# Peripheral.net
KiCad netlist of a schematic drawn in Altium Designer
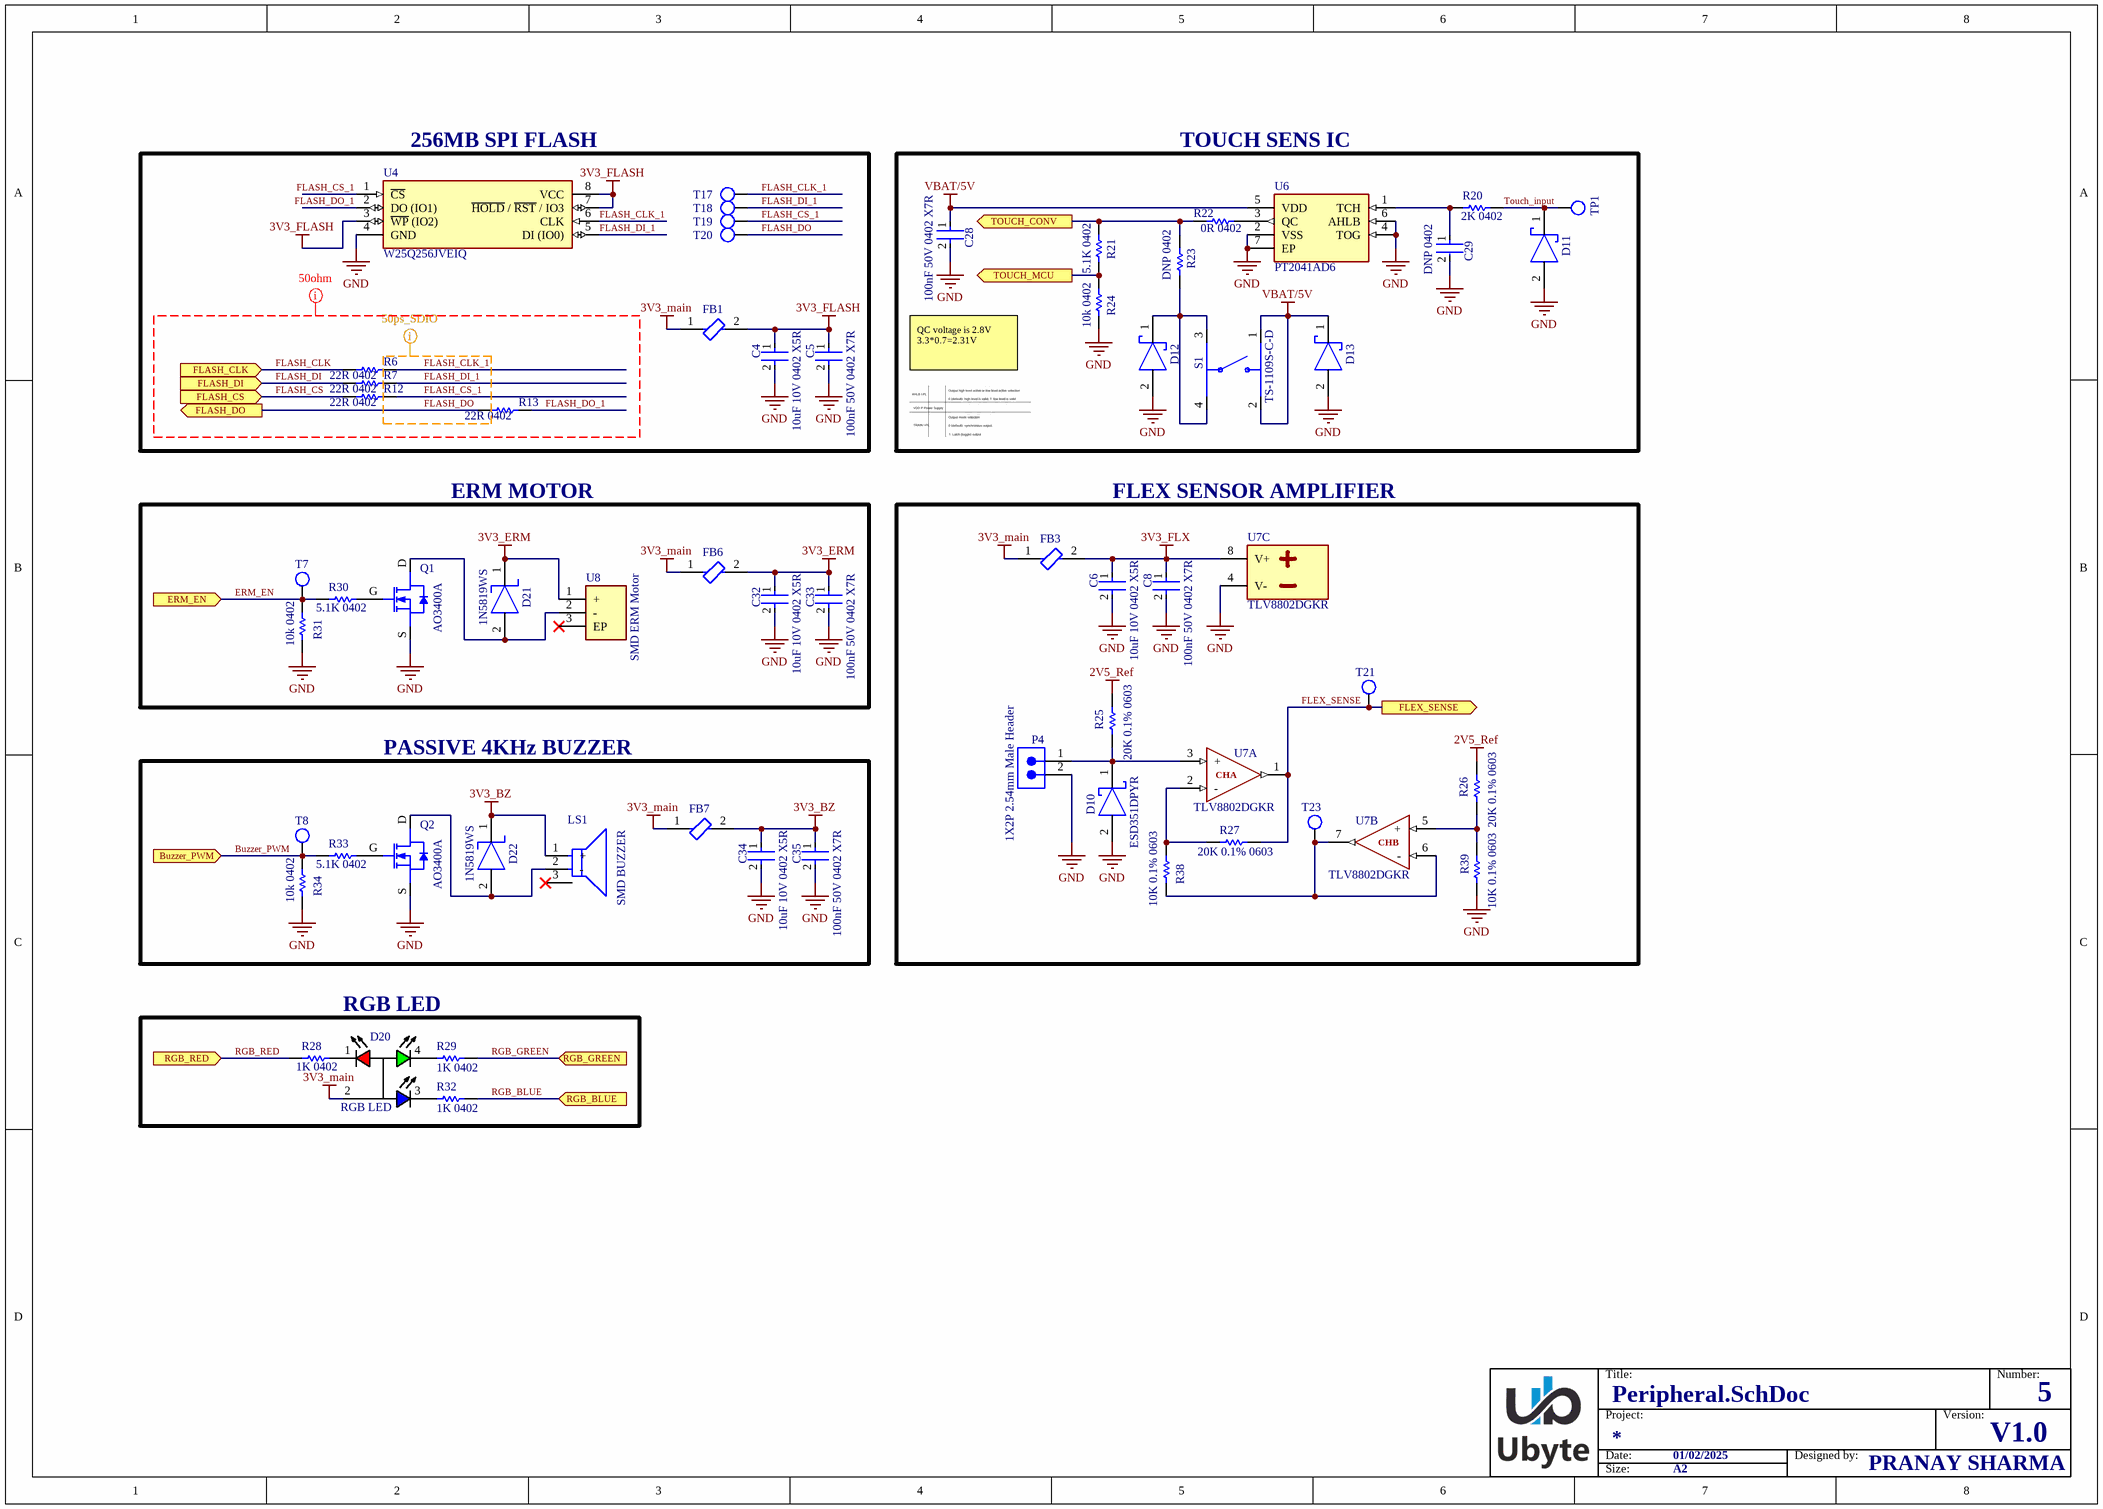
[diagram p0: Peripheral.SchDoc]

(export (version "E")
  (design (tool "Eeschema 10.0.6"))
  (components
    (comp (ref "C4")
      (value "10uF 10V 0402 X5R")
      (footprint "Res, Cap, Ind, LED, FB_Lib:0402 IPC CLASS C CAPACITOR")
      (libsource (lib "Capacitor_Lib") (part "10uF 10V 0402 X5R"))
    )
    (comp (ref "C5")
      (value "100nF 50V 0402 X7R")
      (footprint "Res, Cap, Ind, LED, FB_Lib:0402 IPC CLASS C CAPACITOR")
      (libsource (lib "Capacitor_Lib") (part "100nF 50V 0402 X7R"))
    )
    (comp (ref "C6")
      (value "10uF 10V 0402 X5R")
      (footprint "Res, Cap, Ind, LED, FB_Lib:0402 IPC CLASS C CAPACITOR")
      (libsource (lib "Capacitor_Lib") (part "10uF 10V 0402 X5R"))
    )
    (comp (ref "C8")
      (value "100nF 50V 0402 X7R")
      (footprint "Res, Cap, Ind, LED, FB_Lib:0402 IPC CLASS C CAPACITOR")
      (libsource (lib "Capacitor_Lib") (part "100nF 50V 0402 X7R"))
    )
    (comp (ref "C28")
      (value "100nF 50V 0402 X7R")
      (footprint "Res, Cap, Ind, LED, FB_Lib:0402 IPC CLASS C CAPACITOR")
      (libsource (lib "Capacitor_Lib") (part "100nF 50V 0402 X7R"))
    )
    (comp (ref "C29")
      (value "DNP 0402")
      (footprint "0402 IPC Class C Capacitor")
      (libsource (lib "Integrated Library V1.0") (part "Capacitor 0402"))
    )
    (comp (ref "C32")
      (value "10uF 10V 0402 X5R")
      (footprint "Res, Cap, Ind, LED, FB_Lib:0402 IPC CLASS C CAPACITOR")
      (libsource (lib "Capacitor_Lib") (part "10uF 10V 0402 X5R"))
    )
    (comp (ref "C33")
      (value "100nF 50V 0402 X7R")
      (footprint "Res, Cap, Ind, LED, FB_Lib:0402 IPC CLASS C CAPACITOR")
      (libsource (lib "Capacitor_Lib") (part "100nF 50V 0402 X7R"))
    )
    (comp (ref "C34")
      (value "10uF 10V 0402 X5R")
      (footprint "Res, Cap, Ind, LED, FB_Lib:0402 IPC CLASS C CAPACITOR")
      (libsource (lib "Capacitor_Lib") (part "10uF 10V 0402 X5R"))
    )
    (comp (ref "C35")
      (value "100nF 50V 0402 X7R")
      (footprint "Res, Cap, Ind, LED, FB_Lib:0402 IPC CLASS C CAPACITOR")
      (libsource (lib "Capacitor_Lib") (part "100nF 50V 0402 X7R"))
    )
    (comp (ref "D10")
      (value "ESD351DPYR")
      (footprint "Res, Cap, Ind, LED, FB_Lib:DPY0002A IPC-C")
      (libsource (lib "Diodes_Lib") (part "ESD351DPYR"))
    )
    (comp (ref "D11")
      (value "SP3031-01ETG")
      (footprint "Res, Cap, Ind, LED, FB_Lib:SOD882 IPC-C")
      (libsource (lib "Diodes_Lib") (part "SP3031-01ETG"))
    )
    (comp (ref "D12")
      (value "SP3031-01ETG")
      (footprint "Res, Cap, Ind, LED, FB_Lib:SOD882 IPC-C")
      (libsource (lib "Diodes_Lib") (part "SP3031-01ETG"))
    )
    (comp (ref "D13")
      (value "SP3031-01ETG")
      (footprint "Res, Cap, Ind, LED, FB_Lib:SOD882 IPC-C")
      (libsource (lib "Diodes_Lib") (part "SP3031-01ETG"))
    )
    (comp (ref "D20")
      (value "RGB LED")
      (footprint "Res, Cap, Ind, LED, FB_Lib:NH-B1515RGBA-HF IPC-C")
      (libsource (lib "Diodes_Lib") (part "NH-B1515RGBA-HF"))
    )
    (comp (ref "D21")
      (value "1N5819WS")
      (footprint "Res, Cap, Ind, LED, FB_Lib:SOD-323 IPC-C")
      (libsource (lib "Diodes_Lib") (part "1N5819WS"))
    )
    (comp (ref "D22")
      (value "1N5819WS")
      (footprint "Res, Cap, Ind, LED, FB_Lib:SOD-323 IPC-C")
      (libsource (lib "Diodes_Lib") (part "1N5819WS"))
    )
    (comp (ref "FB1")
      (value "BLM15AX102SN1D")
      (footprint "Res, Cap, Ind, LED, FB_Lib:0402 IPC CLASS C FERRITE BEAD")
      (libsource (lib "Ferrite_Bead_Lib") (part "BLM15AX102SN1D"))
    )
    (comp (ref "FB3")
      (value "BLM15AX102SN1D")
      (footprint "Res, Cap, Ind, LED, FB_Lib:0402 IPC CLASS C FERRITE BEAD")
      (libsource (lib "Ferrite_Bead_Lib") (part "BLM15AX102SN1D"))
    )
    (comp (ref "FB6")
      (value "BLM15AX102SN1D")
      (footprint "Res, Cap, Ind, LED, FB_Lib:0402 IPC CLASS C FERRITE BEAD")
      (libsource (lib "Ferrite_Bead_Lib") (part "BLM15AX102SN1D"))
    )
    (comp (ref "FB7")
      (value "BLM15AX102SN1D")
      (footprint "Res, Cap, Ind, LED, FB_Lib:0402 IPC CLASS C FERRITE BEAD")
      (libsource (lib "Ferrite_Bead_Lib") (part "BLM15AX102SN1D"))
    )
    (comp (ref "LS1")
      (value "SMD BUZZER")
      (footprint "Miscellaneous_Lib:MLT-5020")
      (libsource (lib "Miscellaneous_Lib") (part "MLT-5020"))
    )
    (comp (ref "P4")
      (value "1X2P 2.54mm Male Header")
      (footprint "Connectors_Lib:2P 2.54mm Open Header")
      (libsource (lib "Connectors_Lib") (part "1X2P 2.54mm Male Header"))
    )
    (comp (ref "Q1")
      (value "AO3400A")
      (footprint "Transistors_Lib:SOT-23 IPC-C")
      (libsource (lib "Transistors_Lib") (part "AO3400A"))
    )
    (comp (ref "Q2")
      (value "AO3400A")
      (footprint "Transistors_Lib:SOT-23 IPC-C")
      (libsource (lib "Transistors_Lib") (part "AO3400A"))
    )
    (comp (ref "R6")
      (value "22R 0402")
      (footprint "Res, Cap, Ind, LED, FB_Lib:0402 IPC CLASS C RESISTOR")
      (libsource (lib "Resistor_Lib") (part "22R 1% 0402"))
    )
    (comp (ref "R7")
      (value "22R 0402")
      (footprint "Res, Cap, Ind, LED, FB_Lib:0402 IPC CLASS C RESISTOR")
      (libsource (lib "Resistor_Lib") (part "22R 1% 0402"))
    )
    (comp (ref "R12")
      (value "22R 0402")
      (footprint "Res, Cap, Ind, LED, FB_Lib:0402 IPC CLASS C RESISTOR")
      (libsource (lib "Resistor_Lib") (part "22R 1% 0402"))
    )
    (comp (ref "R13")
      (value "22R 0402")
      (footprint "Res, Cap, Ind, LED, FB_Lib:0402 IPC CLASS C RESISTOR")
      (libsource (lib "Resistor_Lib") (part "22R 1% 0402"))
    )
    (comp (ref "R20")
      (value "2K 0402")
      (footprint "Res, Cap, Ind, LED, FB_Lib:0402 IPC CLASS C RESISTOR")
      (libsource (lib "Resistor_Lib") (part "2K 1% 0402"))
    )
    (comp (ref "R21")
      (value "5.1K 0402")
      (footprint "Res, Cap, Ind, LED, FB_Lib:0402 IPC CLASS C RESISTOR")
      (libsource (lib "Resistor_Lib") (part "5.1K 1% 0402"))
    )
    (comp (ref "R22")
      (value "0R 0402")
      (footprint "Res, Cap, Ind, LED, FB_Lib:0402 IPC CLASS B RESISTOR")
      (libsource (lib "Resistor_Lib") (part "0R 1% 0402"))
    )
    (comp (ref "R23")
      (value "DNP 0402")
      (footprint "Res, Cap, Ind, LED, FB_Lib:0402 IPC CLASS B RESISTOR")
      (libsource (lib "Resistor_Lib") (part "0R 1% 0402"))
    )
    (comp (ref "R24")
      (value "10k 0402")
      (footprint "Res, Cap, Ind, LED, FB_Lib:0402 IPC CLASS C RESISTOR")
      (libsource (lib "Resistor_Lib") (part "10k 1% 0402"))
    )
    (comp (ref "R25")
      (value "20K 0.1% 0603")
      (footprint "Res, Cap, Ind, LED, FB_Lib:0603 IPC CLASS C RESISTOR")
      (libsource (lib "Resistor_Lib") (part "20K 0.1% 0603"))
    )
    (comp (ref "R26")
      (value "20K 0.1% 0603")
      (footprint "Res, Cap, Ind, LED, FB_Lib:0603 IPC CLASS C RESISTOR")
      (libsource (lib "Resistor_Lib") (part "20K 0.1% 0603"))
    )
    (comp (ref "R27")
      (value "20K 0.1% 0603")
      (footprint "Res, Cap, Ind, LED, FB_Lib:0603 IPC CLASS C RESISTOR")
      (libsource (lib "Resistor_Lib") (part "20K 0.1% 0603"))
    )
    (comp (ref "R28")
      (value "1K 0402")
      (footprint "Res, Cap, Ind, LED, FB_Lib:0402 IPC CLASS C RESISTOR")
      (libsource (lib "Resistor_Lib") (part "1K 1% 0402"))
    )
    (comp (ref "R29")
      (value "1K 0402")
      (footprint "Res, Cap, Ind, LED, FB_Lib:0402 IPC CLASS C RESISTOR")
      (libsource (lib "Resistor_Lib") (part "1K 1% 0402"))
    )
    (comp (ref "R30")
      (value "5.1K 0402")
      (footprint "Res, Cap, Ind, LED, FB_Lib:0402 IPC CLASS C RESISTOR")
      (libsource (lib "Resistor_Lib") (part "5.1K 1% 0402"))
    )
    (comp (ref "R31")
      (value "10k 0402")
      (footprint "Res, Cap, Ind, LED, FB_Lib:0402 IPC CLASS C RESISTOR")
      (libsource (lib "Resistor_Lib") (part "10k 1% 0402"))
    )
    (comp (ref "R32")
      (value "1K 0402")
      (footprint "Res, Cap, Ind, LED, FB_Lib:0402 IPC CLASS C RESISTOR")
      (libsource (lib "Resistor_Lib") (part "1K 1% 0402"))
    )
    (comp (ref "R33")
      (value "5.1K 0402")
      (footprint "Res, Cap, Ind, LED, FB_Lib:0402 IPC CLASS C RESISTOR")
      (libsource (lib "Resistor_Lib") (part "5.1K 1% 0402"))
    )
    (comp (ref "R34")
      (value "10k 0402")
      (footprint "Res, Cap, Ind, LED, FB_Lib:0402 IPC CLASS C RESISTOR")
      (libsource (lib "Resistor_Lib") (part "10k 1% 0402"))
    )
    (comp (ref "R38")
      (value "10K 0.1% 0603")
      (footprint "Res, Cap, Ind, LED, FB_Lib:0603 IPC CLASS C RESISTOR")
      (libsource (lib "Resistor_Lib") (part "10K 0.1% 0603"))
    )
    (comp (ref "R39")
      (value "10K 0.1% 0603")
      (footprint "Res, Cap, Ind, LED, FB_Lib:0603 IPC CLASS C RESISTOR")
      (libsource (lib "Resistor_Lib") (part "10K 0.1% 0603"))
    )
    (comp (ref "S1")
      (value "TS-1109S-C-D")
      (footprint "TS-1127-C")
      (libsource (lib "Integrated Library V1.0") (part "TS-1127-C"))
    )
    (comp (ref "T7")
      (value "~")
      (footprint "Test Point TH")
      (libsource (lib "Miscellaneous_Lib") (part "Test Point TH"))
    )
    (comp (ref "T8")
      (value "~")
      (footprint "Test Point TH")
      (libsource (lib "Miscellaneous_Lib") (part "Test Point TH"))
    )
    (comp (ref "T17")
      (value "TP")
      (footprint "Miscellaneous_Lib:Testpoint1")
      (libsource (lib "Miscellaneous_Lib") (part "Testpoint1"))
    )
    (comp (ref "T18")
      (value "TP")
      (footprint "Miscellaneous_Lib:Testpoint1")
      (libsource (lib "Miscellaneous_Lib") (part "Testpoint1"))
    )
    (comp (ref "T19")
      (value "TP")
      (footprint "Miscellaneous_Lib:Testpoint1")
      (libsource (lib "Miscellaneous_Lib") (part "Testpoint1"))
    )
    (comp (ref "T20")
      (value "TP")
      (footprint "Miscellaneous_Lib:Testpoint1")
      (libsource (lib "Miscellaneous_Lib") (part "Testpoint1"))
    )
    (comp (ref "T21")
      (value "TP")
      (footprint "Miscellaneous_Lib:Testpoint1")
      (libsource (lib "Miscellaneous_Lib") (part "Testpoint1"))
    )
    (comp (ref "T23")
      (value "TP")
      (footprint "Miscellaneous_Lib:Testpoint1")
      (libsource (lib "Miscellaneous_Lib") (part "Testpoint1"))
    )
    (comp (ref "TP1")
      (value "Test Point TH")
      (footprint "Test Point TH")
      (libsource (lib "Integrated Library V1.0") (part "Test Point TH"))
    )
    (comp (ref "U4")
      (value "W25Q256JVEIQ")
      (footprint "Integrated_Circuits_Lib:8-Pad WSON 8x6-mm IPC-C")
      (libsource (lib "Integrated_Circuits_Lib") (part "W25Q256JVEIQ"))
    )
    (comp (ref "U6")
      (value "PT2041AD6")
      (footprint "Integrated_Circuits_Lib:DFN2X2-6L IPC-C")
      (libsource (lib "Integrated_Circuits_Lib") (part "PT2041AD6"))
    )
    (comp (ref "U7")
      (value "TLV8802DGKR")
      (footprint "Integrated_Circuits_Lib:DGK0008A IPC-C")
      (libsource (lib "Integrated_Circuits_Lib") (part "TLV8802DGKR"))
    )
    (comp (ref "U8")
      (value "SMD ERM Motor")
      (footprint "Miscellaneous_Lib:Z3OC1T8219731")
      (libsource (lib "Miscellaneous_Lib") (part "Z3OC1T8219731"))
    )
  )
  (nets
    (net (code "1") (name "/Buzzer_PWM") (class "Default")
      (node (ref "R33") (pin "1") (pinfunction "1_1") (pintype "passive"))
      (node (ref "R34") (pin "2") (pinfunction "2_2") (pintype "passive"))
      (node (ref "T8") (pin "0") (pinfunction "0_0") (pintype "passive"))
    )
    (net (code "2") (name "/ERM_EN") (class "Default")
      (node (ref "R30") (pin "1") (pinfunction "1_1") (pintype "passive"))
      (node (ref "R31") (pin "2") (pinfunction "2_2") (pintype "passive"))
      (node (ref "T7") (pin "0") (pinfunction "0_0") (pintype "passive"))
    )
    (net (code "3") (name "/FLASH_CLK") (class "Default")
      (node (ref "R6") (pin "1") (pinfunction "1_1") (pintype "passive"))
    )
    (net (code "4") (name "/FLASH_CLK_1") (class "Default")
      (node (ref "R6") (pin "2") (pinfunction "2_2") (pintype "passive"))
      (node (ref "T17") (pin "0") (pinfunction "0_0") (pintype "passive"))
      (node (ref "U4") (pin "6") (pinfunction "CLK_6") (pintype "input"))
    )
    (net (code "5") (name "/FLASH_CS") (class "Default")
      (node (ref "R12") (pin "1") (pinfunction "1_1") (pintype "passive"))
    )
    (net (code "6") (name "/FLASH_CS_1") (class "Default")
      (node (ref "R12") (pin "2") (pinfunction "2_2") (pintype "passive"))
      (node (ref "T19") (pin "0") (pinfunction "0_0") (pintype "passive"))
      (node (ref "U4") (pin "1") (pinfunction "~{CS}_1") (pintype "input"))
    )
    (net (code "7") (name "/FLASH_DI") (class "Default")
      (node (ref "R7") (pin "1") (pinfunction "1_1") (pintype "passive"))
    )
    (net (code "8") (name "/FLASH_DI_1") (class "Default")
      (node (ref "R7") (pin "2") (pinfunction "2_2") (pintype "passive"))
      (node (ref "T18") (pin "0") (pinfunction "0_0") (pintype "passive"))
      (node (ref "U4") (pin "5") (pinfunction "DI_(IO0)_5") (pintype "bidirectional"))
    )
    (net (code "9") (name "/FLASH_DO") (class "Default")
      (node (ref "R13") (pin "1") (pinfunction "1_1") (pintype "passive"))
      (node (ref "T20") (pin "0") (pinfunction "0_0") (pintype "passive"))
    )
    (net (code "10") (name "/FLASH_DO_1") (class "Default")
      (node (ref "R13") (pin "2") (pinfunction "2_2") (pintype "passive"))
      (node (ref "U4") (pin "2") (pinfunction "DO_(IO1)_2") (pintype "bidirectional"))
    )
    (net (code "11") (name "/FLEX_SENSE") (class "Default")
      (node (ref "R27") (pin "1") (pinfunction "1_1") (pintype "passive"))
      (node (ref "T21") (pin "0") (pinfunction "0_0") (pintype "passive"))
      (node (ref "U7") (pin "1") (pinfunction "OUT1_1") (pintype "output"))
    )
    (net (code "12") (name "/RGB_BLUE") (class "Default")
      (node (ref "R32") (pin "2") (pinfunction "2_2") (pintype "passive"))
    )
    (net (code "13") (name "/RGB_GREEN") (class "Default")
      (node (ref "R29") (pin "2") (pinfunction "2_2") (pintype "passive"))
    )
    (net (code "14") (name "/RGB_RED") (class "Default")
      (node (ref "R28") (pin "1") (pinfunction "1_1") (pintype "passive"))
    )
    (net (code "15") (name "/TOUCH_CONV") (class "Default")
      (node (ref "R21") (pin "2") (pinfunction "2_2") (pintype "passive"))
      (node (ref "R22") (pin "2") (pinfunction "2_2") (pintype "passive"))
      (node (ref "R23") (pin "1") (pinfunction "1_1") (pintype "passive"))
    )
    (net (code "16") (name "/TOUCH_MCU") (class "Default")
      (node (ref "R21") (pin "1") (pinfunction "1_1") (pintype "passive"))
      (node (ref "R24") (pin "1") (pinfunction "1_1") (pintype "passive"))
    )
    (net (code "17") (name "/Touch_input") (class "Default")
      (node (ref "D11") (pin "1") (pinfunction "C_1") (pintype "passive"))
      (node (ref "R20") (pin "2") (pinfunction "2_2") (pintype "passive"))
      (node (ref "TP1") (pin "0") (pinfunction "0_0") (pintype "passive"))
    )
    (net (code "18") (name "2V5_Ref") (class "Default")
      (node (ref "R25") (pin "2") (pinfunction "2_2") (pintype "passive"))
      (node (ref "R26") (pin "2") (pinfunction "2_2") (pintype "passive"))
    )
    (net (code "19") (name "3V3_BZ") (class "Default")
      (node (ref "C34") (pin "1") (pinfunction "1_1") (pintype "passive"))
      (node (ref "C35") (pin "1") (pinfunction "1_1") (pintype "passive"))
      (node (ref "D22") (pin "1") (pinfunction "C_1") (pintype "passive"))
      (node (ref "FB7") (pin "2") (pinfunction "2_2") (pintype "passive"))
      (node (ref "LS1") (pin "1") (pinfunction "+_1") (pintype "passive"))
    )
    (net (code "20") (name "3V3_ERM") (class "Default")
      (node (ref "C32") (pin "1") (pinfunction "1_1") (pintype "passive"))
      (node (ref "C33") (pin "1") (pinfunction "1_1") (pintype "passive"))
      (node (ref "D21") (pin "1") (pinfunction "C_1") (pintype "passive"))
      (node (ref "FB6") (pin "2") (pinfunction "2_2") (pintype "passive"))
      (node (ref "U8") (pin "1") (pinfunction "+_1") (pintype "power_in"))
    )
    (net (code "21") (name "3V3_FLASH") (class "Default")
      (node (ref "C4") (pin "1") (pinfunction "1_1") (pintype "passive"))
      (node (ref "C5") (pin "1") (pinfunction "1_1") (pintype "passive"))
      (node (ref "FB1") (pin "2") (pinfunction "2_2") (pintype "passive"))
      (node (ref "U4") (pin "3") (pinfunction "~{WP}_(IO2)_3") (pintype "bidirectional"))
      (node (ref "U4") (pin "7") (pinfunction "~{HOLD}_/_~{RST}_/_IO3_7") (pintype "bidirectional"))
      (node (ref "U4") (pin "8") (pinfunction "VCC_8") (pintype "power_in"))
    )
    (net (code "22") (name "3V3_FLX") (class "Default")
      (node (ref "C6") (pin "1") (pinfunction "1_1") (pintype "passive"))
      (node (ref "C8") (pin "1") (pinfunction "1_1") (pintype "passive"))
      (node (ref "FB3") (pin "2") (pinfunction "2_2") (pintype "passive"))
      (node (ref "U7") (pin "8") (pinfunction "V+_8") (pintype "power_in"))
    )
    (net (code "23") (name "3V3_main") (class "Default")
      (node (ref "D20") (pin "2") (pinfunction "COM+_2") (pintype "passive"))
      (node (ref "FB1") (pin "1") (pinfunction "1_1") (pintype "passive"))
      (node (ref "FB3") (pin "1") (pinfunction "1_1") (pintype "passive"))
      (node (ref "FB6") (pin "1") (pinfunction "1_1") (pintype "passive"))
      (node (ref "FB7") (pin "1") (pinfunction "1_1") (pintype "passive"))
    )
    (net (code "24") (name "GND") (class "Default")
      (node (ref "C28") (pin "2") (pinfunction "2_2") (pintype "passive"))
      (node (ref "C29") (pin "2") (pinfunction "2_2") (pintype "passive"))
      (node (ref "C32") (pin "2") (pinfunction "2_2") (pintype "passive"))
      (node (ref "C33") (pin "2") (pinfunction "2_2") (pintype "passive"))
      (node (ref "C34") (pin "2") (pinfunction "2_2") (pintype "passive"))
      (node (ref "C35") (pin "2") (pinfunction "2_2") (pintype "passive"))
      (node (ref "C4") (pin "2") (pinfunction "2_2") (pintype "passive"))
      (node (ref "C5") (pin "2") (pinfunction "2_2") (pintype "passive"))
      (node (ref "C6") (pin "2") (pinfunction "2_2") (pintype "passive"))
      (node (ref "C8") (pin "2") (pinfunction "2_2") (pintype "passive"))
      (node (ref "D10") (pin "2") (pinfunction "K2_2") (pintype "passive"))
      (node (ref "D11") (pin "2") (pinfunction "A_2") (pintype "passive"))
      (node (ref "D12") (pin "2") (pinfunction "A_2") (pintype "passive"))
      (node (ref "D13") (pin "2") (pinfunction "A_2") (pintype "passive"))
      (node (ref "P4") (pin "2") (pinfunction "2_2") (pintype "passive"))
      (node (ref "Q1") (pin "S") (pinfunction "SOURCE_S") (pintype "passive"))
      (node (ref "Q2") (pin "S") (pinfunction "SOURCE_S") (pintype "passive"))
      (node (ref "R24") (pin "2") (pinfunction "2_2") (pintype "passive"))
      (node (ref "R31") (pin "1") (pinfunction "1_1") (pintype "passive"))
      (node (ref "R34") (pin "1") (pinfunction "1_1") (pintype "passive"))
      (node (ref "R39") (pin "1") (pinfunction "1_1") (pintype "passive"))
      (node (ref "U4") (pin "4") (pinfunction "GND_4") (pintype "power_in"))
      (node (ref "U6") (pin "2") (pinfunction "VSS_2") (pintype "power_in"))
      (node (ref "U6") (pin "4") (pinfunction "TOG_4") (pintype "input"))
      (node (ref "U6") (pin "6") (pinfunction "AHLB_6") (pintype "input"))
      (node (ref "U6") (pin "7") (pinfunction "EP_7") (pintype "power_in"))
      (node (ref "U7") (pin "4") (pinfunction "V-_4") (pintype "power_in"))
    )
    (net (code "25") (name "Net-(D10-K1)") (class "Default")
      (node (ref "D10") (pin "1") (pinfunction "K1_1") (pintype "passive"))
      (node (ref "P4") (pin "1") (pinfunction "1_1") (pintype "passive"))
      (node (ref "R25") (pin "1") (pinfunction "1_1") (pintype "passive"))
      (node (ref "U7") (pin "3") (pinfunction "+_3") (pintype "input"))
    )
    (net (code "26") (name "Net-(D12-C)") (class "Default")
      (node (ref "D12") (pin "1") (pinfunction "C_1") (pintype "passive"))
      (node (ref "R23") (pin "2") (pinfunction "2_2") (pintype "passive"))
      (node (ref "S1") (pin "3") (pinfunction "3_3") (pintype "passive"))
      (node (ref "S1") (pin "4") (pinfunction "4_4") (pintype "passive"))
    )
    (net (code "27") (name "Net-(D20-B-)") (class "Default")
      (node (ref "D20") (pin "3") (pinfunction "B-_3") (pintype "passive"))
      (node (ref "R32") (pin "1") (pinfunction "1_1") (pintype "passive"))
    )
    (net (code "28") (name "Net-(D20-G-)") (class "Default")
      (node (ref "D20") (pin "4") (pinfunction "G-_4") (pintype "passive"))
      (node (ref "R29") (pin "1") (pinfunction "1_1") (pintype "passive"))
    )
    (net (code "29") (name "Net-(D20-R-)") (class "Default")
      (node (ref "D20") (pin "1") (pinfunction "R-_1") (pintype "passive"))
      (node (ref "R28") (pin "2") (pinfunction "2_2") (pintype "passive"))
    )
    (net (code "30") (name "Net-(D21-A)") (class "Default")
      (node (ref "D21") (pin "2") (pinfunction "A_2") (pintype "passive"))
      (node (ref "Q1") (pin "D") (pinfunction "DRAIN_D") (pintype "passive"))
      (node (ref "U8") (pin "2") (pinfunction "-_2") (pintype "power_in"))
    )
    (net (code "31") (name "Net-(D22-A)") (class "Default")
      (node (ref "D22") (pin "2") (pinfunction "A_2") (pintype "passive"))
      (node (ref "LS1") (pin "2") (pinfunction "-_2") (pintype "passive"))
      (node (ref "Q2") (pin "D") (pinfunction "DRAIN_D") (pintype "passive"))
    )
    (net (code "32") (name "Net-(Q1-GATE)") (class "Default")
      (node (ref "Q1") (pin "G") (pinfunction "GATE_G") (pintype "passive"))
      (node (ref "R30") (pin "2") (pinfunction "2_2") (pintype "passive"))
    )
    (net (code "33") (name "Net-(Q2-GATE)") (class "Default")
      (node (ref "Q2") (pin "G") (pinfunction "GATE_G") (pintype "passive"))
      (node (ref "R33") (pin "2") (pinfunction "2_2") (pintype "passive"))
    )
    (net (code "34") (name "Net-(U6-QC)") (class "Default")
      (node (ref "R22") (pin "1") (pinfunction "1_1") (pintype "passive"))
      (node (ref "U6") (pin "3") (pinfunction "QC_3") (pintype "output"))
    )
    (net (code "35") (name "Net-(U6-TCH)") (class "Default")
      (node (ref "C29") (pin "1") (pinfunction "1_1") (pintype "passive"))
      (node (ref "R20") (pin "1") (pinfunction "1_1") (pintype "passive"))
      (node (ref "U6") (pin "1") (pinfunction "TCH_1") (pintype "input"))
    )
    (net (code "36") (name "Net-(U7A--)") (class "Default")
      (node (ref "R27") (pin "2") (pinfunction "2_2") (pintype "passive"))
      (node (ref "R38") (pin "2") (pinfunction "2_2") (pintype "passive"))
      (node (ref "U7") (pin "2") (pinfunction "-_2") (pintype "input"))
    )
    (net (code "37") (name "Net-(U7B-+)") (class "Default")
      (node (ref "R26") (pin "1") (pinfunction "1_1") (pintype "passive"))
      (node (ref "R39") (pin "2") (pinfunction "2_2") (pintype "passive"))
      (node (ref "U7") (pin "5") (pinfunction "+_5") (pintype "input"))
    )
    (net (code "38") (name "Net-(U7B--)") (class "Default")
      (node (ref "R38") (pin "1") (pinfunction "1_1") (pintype "passive"))
      (node (ref "T23") (pin "0") (pinfunction "0_0") (pintype "passive"))
      (node (ref "U7") (pin "6") (pinfunction "-_6") (pintype "input"))
      (node (ref "U7") (pin "7") (pinfunction "OUT1_7") (pintype "output"))
    )
    (net (code "39") (name "VBAT{slash}5V") (class "Default")
      (node (ref "C28") (pin "1") (pinfunction "1_1") (pintype "passive"))
      (node (ref "D13") (pin "1") (pinfunction "C_1") (pintype "passive"))
      (node (ref "S1") (pin "1") (pinfunction "1_1") (pintype "passive"))
      (node (ref "S1") (pin "2") (pinfunction "2_2") (pintype "passive"))
      (node (ref "U6") (pin "5") (pinfunction "VDD_5") (pintype "power_in"))
    )
    (net (code "40") (name "unconnected-(LS1-A-Pad3)") (class "Default")
      (node (ref "LS1") (pin "3") (pinfunction "A_3") (pintype "passive+no_connect"))
    )
    (net (code "41") (name "unconnected-(U8-EP-Pad3)") (class "Default")
      (node (ref "U8") (pin "3") (pinfunction "EP_3") (pintype "passive+no_connect"))
    )
  )
)
